# MRF49XAmboard.net
KiCad netlist of a schematic drawn in Altium Designer
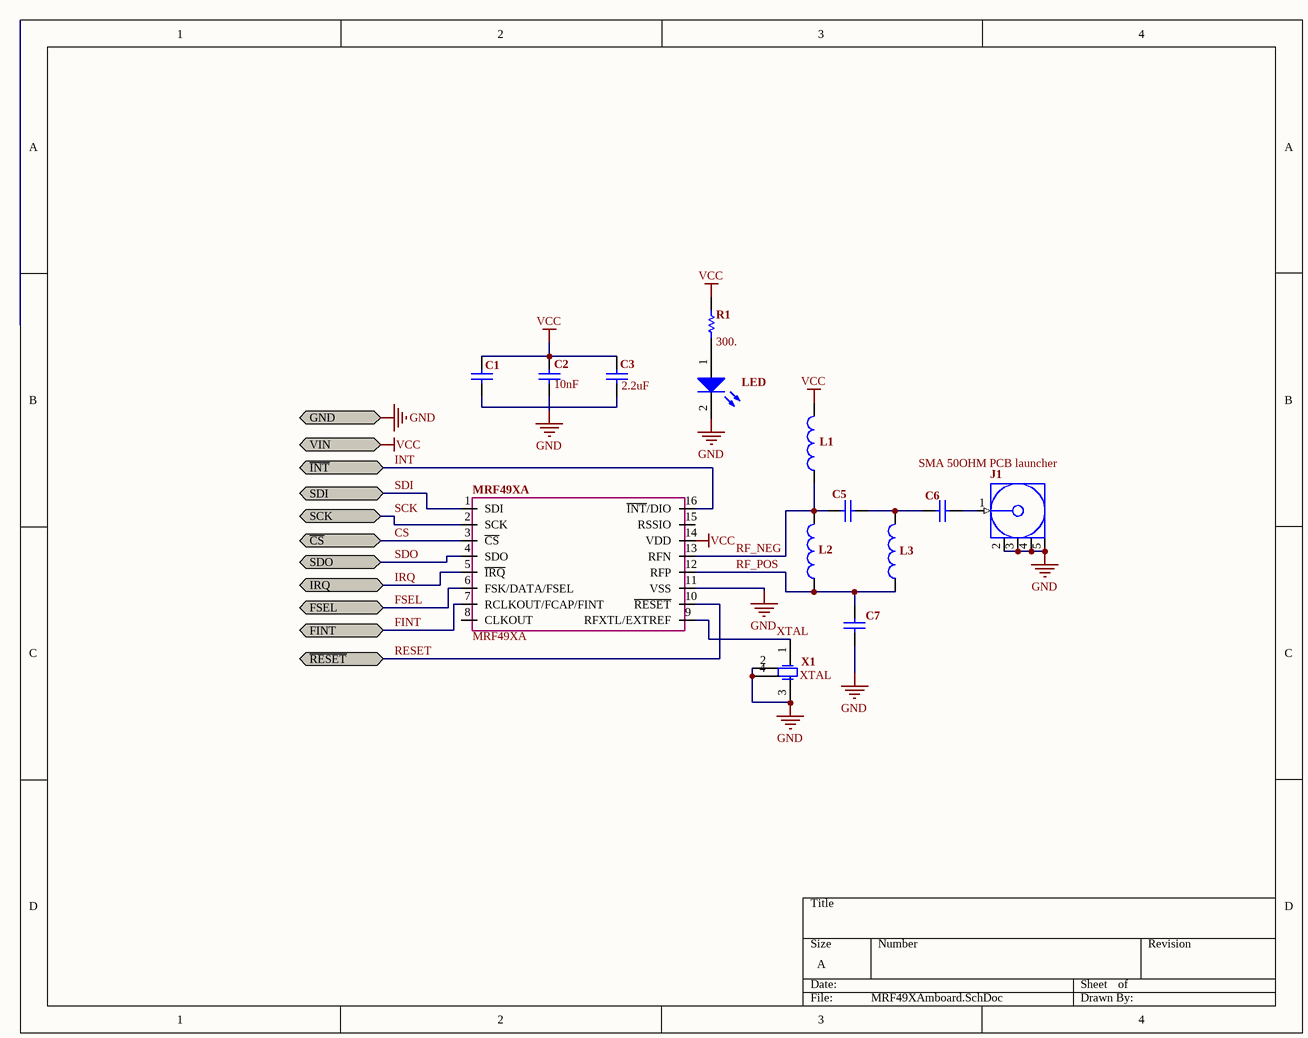
[diagram p0: MRF49XAmboard.SchDoc]

(export (version "E")
  (design (tool "Eeschema 10.0.6"))
  (components
    (comp (ref "C1")
      (value "Cap")
      (footprint "LSI:1608[0603] - SERIGRAFIADO")
      (description "Capacitor")
      (fields (field (name "PUBLISHER") "Altium Limited"))
      (libsource (lib "Miscellaneous Devices") (part "Cap"))
    )
    (comp (ref "C2")
      (value "10nF")
      (footprint "LSI:1608[0603] - Serigrafiado")
      (description "Capacitor")
      (fields (field (name "Comment") "Cap") (field (name "PUBLISHER") "Altium Limited"))
      (libsource (lib "Miscellaneous Devices") (part "Cap"))
    )
    (comp (ref "C3")
      (value "2.2uF")
      (footprint "CAPC3216N")
      (description "Capacitor")
      (fields (field (name "Comment") "Cap") (field (name "PUBLISHER") "Altium Limited"))
      (libsource (lib "agus_lib") (part "Cap"))
    )
    (comp (ref "C5")
      (value "Cap")
      (footprint "1608[0603] - serigrafiado")
      (description "Capacitor")
      (fields (field (name "PUBLISHER") "Altium Limited"))
      (libsource (lib "Miscellaneous Devices") (part "Cap"))
    )
    (comp (ref "C6")
      (value "Cap")
      (footprint "1608[0603] - serigrafiado")
      (description "Capacitor")
      (fields (field (name "PUBLISHER") "Altium Limited"))
      (libsource (lib "Miscellaneous Devices") (part "Cap"))
    )
    (comp (ref "C7")
      (value "Cap")
      (footprint "1608[0603] - serigrafiado")
      (description "Capacitor")
      (fields (field (name "PUBLISHER") "Altium Limited"))
      (libsource (lib "Miscellaneous Devices") (part "Cap"))
    )
    (comp (ref "J1")
      (value "SMA 50OHM PCB launcher")
      (footprint "SMA PCB LAUNCHER")
      (description "SMA RF Coaxial PCB Connector, SM, Vertical Mount Socket, 50 Ohm Impedance")
      (fields (field (name "PUBLISHER") "Altium Limited"))
      (libsource (lib "agus_lib") (part "SMA 50OHM PCB launcher"))
    )
    (comp (ref "L1")
      (value "L")
      (footprint "1608[0603] - serigrafiado")
      (description "Inductor")
      (fields
        (field (name "MANUFACTURER") "Generic Components")
        (field (name "PUBLISHER") "Altium Hobart Technology Centre")
      )
      (libsource (lib "LSI") (part "L"))
    )
    (comp (ref "L2")
      (value "L")
      (footprint "1608[0603] - serigrafiado")
      (description "Inductor")
      (fields
        (field (name "MANUFACTURER") "Generic Components")
        (field (name "PUBLISHER") "Altium Hobart Technology Centre")
      )
      (libsource (lib "LSI") (part "L"))
    )
    (comp (ref "L3")
      (value "L")
      (footprint "1608[0603] - serigrafiado")
      (description "Inductor")
      (fields
        (field (name "MANUFACTURER") "Generic Components")
        (field (name "PUBLISHER") "Altium Hobart Technology Centre")
      )
      (libsource (lib "LSI") (part "L"))
    )
    (comp (ref "LED")
      (value "LED_SMD_Hg")
      (footprint "1608[0603] - SERIGRAFIADO")
      (description "Typical BLUE SiC LED")
      (fields
        (field (name "MANUFACTURER") "Generic Components")
        (field (name "PUBLISHER") "Altium Hobart Technology Centre")
      )
      (libsource (lib "LSI") (part "LED_SMD_Hg"))
    )
    (comp (ref "MRF49XA")
      (value "MRF49XA")
      (footprint "MRF49XA")
      (description "Sub-GHz RF transceiver supporting the 433/868/915MHz ISM frequency band")
      (libsource (lib "agus_lib") (part "MRF49XA"))
    )
    (comp (ref "R1")
      (value "300.")
      (footprint "1608[0603] - SERIGRAFIADO")
      (description "Resistor")
      (fields (field (name "Comment") "Res1") (field (name "PUBLISHER") "Altium Limited"))
      (libsource (lib "Miscellaneous Devices") (part "Res1"))
    )
    (comp (ref "X1")
      (value "XTAL")
      (footprint "XTC CRYSTAL")
      (description "Crystal Oscillator")
      (fields (field (name "PUBLISHER") "Altium Limited"))
      (libsource (lib "agus_lib") (part "XTAL"))
    )
  )
  (nets
    (net (code "1") (name "/CS") (class "Default")
      (node (ref "MRF49XA") (pin "3") (pinfunction "~{CS}_3") (pintype "passive"))
    )
    (net (code "2") (name "/FINT") (class "Default")
      (node (ref "MRF49XA") (pin "7") (pinfunction "RCLKOUT/FCAP/FINT_7") (pintype "passive"))
    )
    (net (code "3") (name "/FSEL") (class "Default")
      (node (ref "MRF49XA") (pin "6") (pinfunction "FSK/DATA/FSEL_6") (pintype "passive"))
    )
    (net (code "4") (name "/INT") (class "Default")
      (node (ref "MRF49XA") (pin "16") (pinfunction "~{INT}/DIO_16") (pintype "passive"))
    )
    (net (code "5") (name "/IRQ") (class "Default")
      (node (ref "MRF49XA") (pin "5") (pinfunction "~{IRQ}_5") (pintype "passive"))
    )
    (net (code "6") (name "/RESET") (class "Default")
      (node (ref "MRF49XA") (pin "10") (pinfunction "~{RESET}_10") (pintype "passive"))
    )
    (net (code "7") (name "/RF_NEG") (class "Default")
      (node (ref "C5") (pin "2") (pinfunction "2_2") (pintype "passive"))
      (node (ref "L1") (pin "1") (pinfunction "1_1") (pintype "passive"))
      (node (ref "L2") (pin "2") (pinfunction "2_2") (pintype "passive"))
      (node (ref "MRF49XA") (pin "13") (pinfunction "RFN_13") (pintype "passive"))
    )
    (net (code "8") (name "/RF_POS") (class "Default")
      (node (ref "C7") (pin "2") (pinfunction "2_2") (pintype "passive"))
      (node (ref "L2") (pin "1") (pinfunction "1_1") (pintype "passive"))
      (node (ref "L3") (pin "1") (pinfunction "1_1") (pintype "passive"))
      (node (ref "MRF49XA") (pin "12") (pinfunction "RFP_12") (pintype "passive"))
    )
    (net (code "9") (name "/SCK") (class "Default")
      (node (ref "MRF49XA") (pin "2") (pinfunction "SCK_2") (pintype "passive"))
    )
    (net (code "10") (name "/SDI") (class "Default")
      (node (ref "MRF49XA") (pin "1") (pinfunction "SDI_1") (pintype "passive"))
    )
    (net (code "11") (name "/SDO") (class "Default")
      (node (ref "MRF49XA") (pin "4") (pinfunction "SDO_4") (pintype "passive"))
    )
    (net (code "12") (name "/XTAL") (class "Default")
      (node (ref "MRF49XA") (pin "9") (pinfunction "RFXTL/EXTREF_9") (pintype "passive"))
      (node (ref "X1") (pin "1") (pinfunction "OSC1_1") (pintype "passive"))
    )
    (net (code "13") (name "GND") (class "Default")
      (node (ref "C2") (pin "1") (pinfunction "1_1") (pintype "passive"))
      (node (ref "C7") (pin "1") (pinfunction "1_1") (pintype "passive"))
      (node (ref "J1") (pin "2") (pinfunction "GND_2") (pintype "power_in"))
      (node (ref "J1") (pin "3") (pinfunction "GND_3") (pintype "power_in"))
      (node (ref "J1") (pin "4") (pinfunction "GND_4") (pintype "power_in"))
      (node (ref "J1") (pin "5") (pinfunction "GND_5") (pintype "power_in"))
      (node (ref "LED") (pin "2") (pinfunction "K_2") (pintype "passive"))
      (node (ref "MRF49XA") (pin "11") (pinfunction "VSS_11") (pintype "passive"))
      (node (ref "X1") (pin "2") (pinfunction "GND_2") (pintype "passive"))
      (node (ref "X1") (pin "3") (pinfunction "OSC2_3") (pintype "passive"))
      (node (ref "X1") (pin "4") (pinfunction "GND_4") (pintype "passive"))
    )
    (net (code "14") (name "Net-(C1-Pad1)") (class "Default")
      (node (ref "C1") (pin "1") (pinfunction "1_1") (pintype "passive"))
      (node (ref "C3") (pin "1") (pinfunction "1_1") (pintype "passive"))
    )
    (net (code "15") (name "Net-(C5-Pad1)") (class "Default")
      (node (ref "C5") (pin "1") (pinfunction "1_1") (pintype "passive"))
      (node (ref "C6") (pin "2") (pinfunction "2_2") (pintype "passive"))
      (node (ref "L3") (pin "2") (pinfunction "2_2") (pintype "passive"))
    )
    (net (code "16") (name "Net-(J1-Signal)") (class "Default")
      (node (ref "C6") (pin "1") (pinfunction "1_1") (pintype "passive"))
      (node (ref "J1") (pin "1") (pinfunction "Signal_1") (pintype "input"))
    )
    (net (code "17") (name "Net-(LED-A)") (class "Default")
      (node (ref "LED") (pin "1") (pinfunction "A_1") (pintype "passive"))
      (node (ref "R1") (pin "1") (pinfunction "1_1") (pintype "passive"))
    )
    (net (code "18") (name "VCC") (class "Default")
      (node (ref "C1") (pin "2") (pinfunction "2_2") (pintype "passive"))
      (node (ref "C2") (pin "2") (pinfunction "2_2") (pintype "passive"))
      (node (ref "C3") (pin "2") (pinfunction "2_2") (pintype "passive"))
      (node (ref "L1") (pin "2") (pinfunction "2_2") (pintype "passive"))
      (node (ref "MRF49XA") (pin "14") (pinfunction "VDD_14") (pintype "passive"))
      (node (ref "R1") (pin "2") (pinfunction "2_2") (pintype "passive"))
    )
    (net (code "19") (name "unconnected-(MRF49XA-CLKOUT-Pad8)") (class "Default")
      (node (ref "MRF49XA") (pin "8") (pinfunction "CLKOUT_8") (pintype "passive"))
    )
    (net (code "20") (name "unconnected-(MRF49XA-RSSIO-Pad15)") (class "Default")
      (node (ref "MRF49XA") (pin "15") (pinfunction "RSSIO_15") (pintype "passive"))
    )
  )
)
